# Croduino_Basic_v1_2.net
KiCad netlist of a schematic drawn in EAGLE
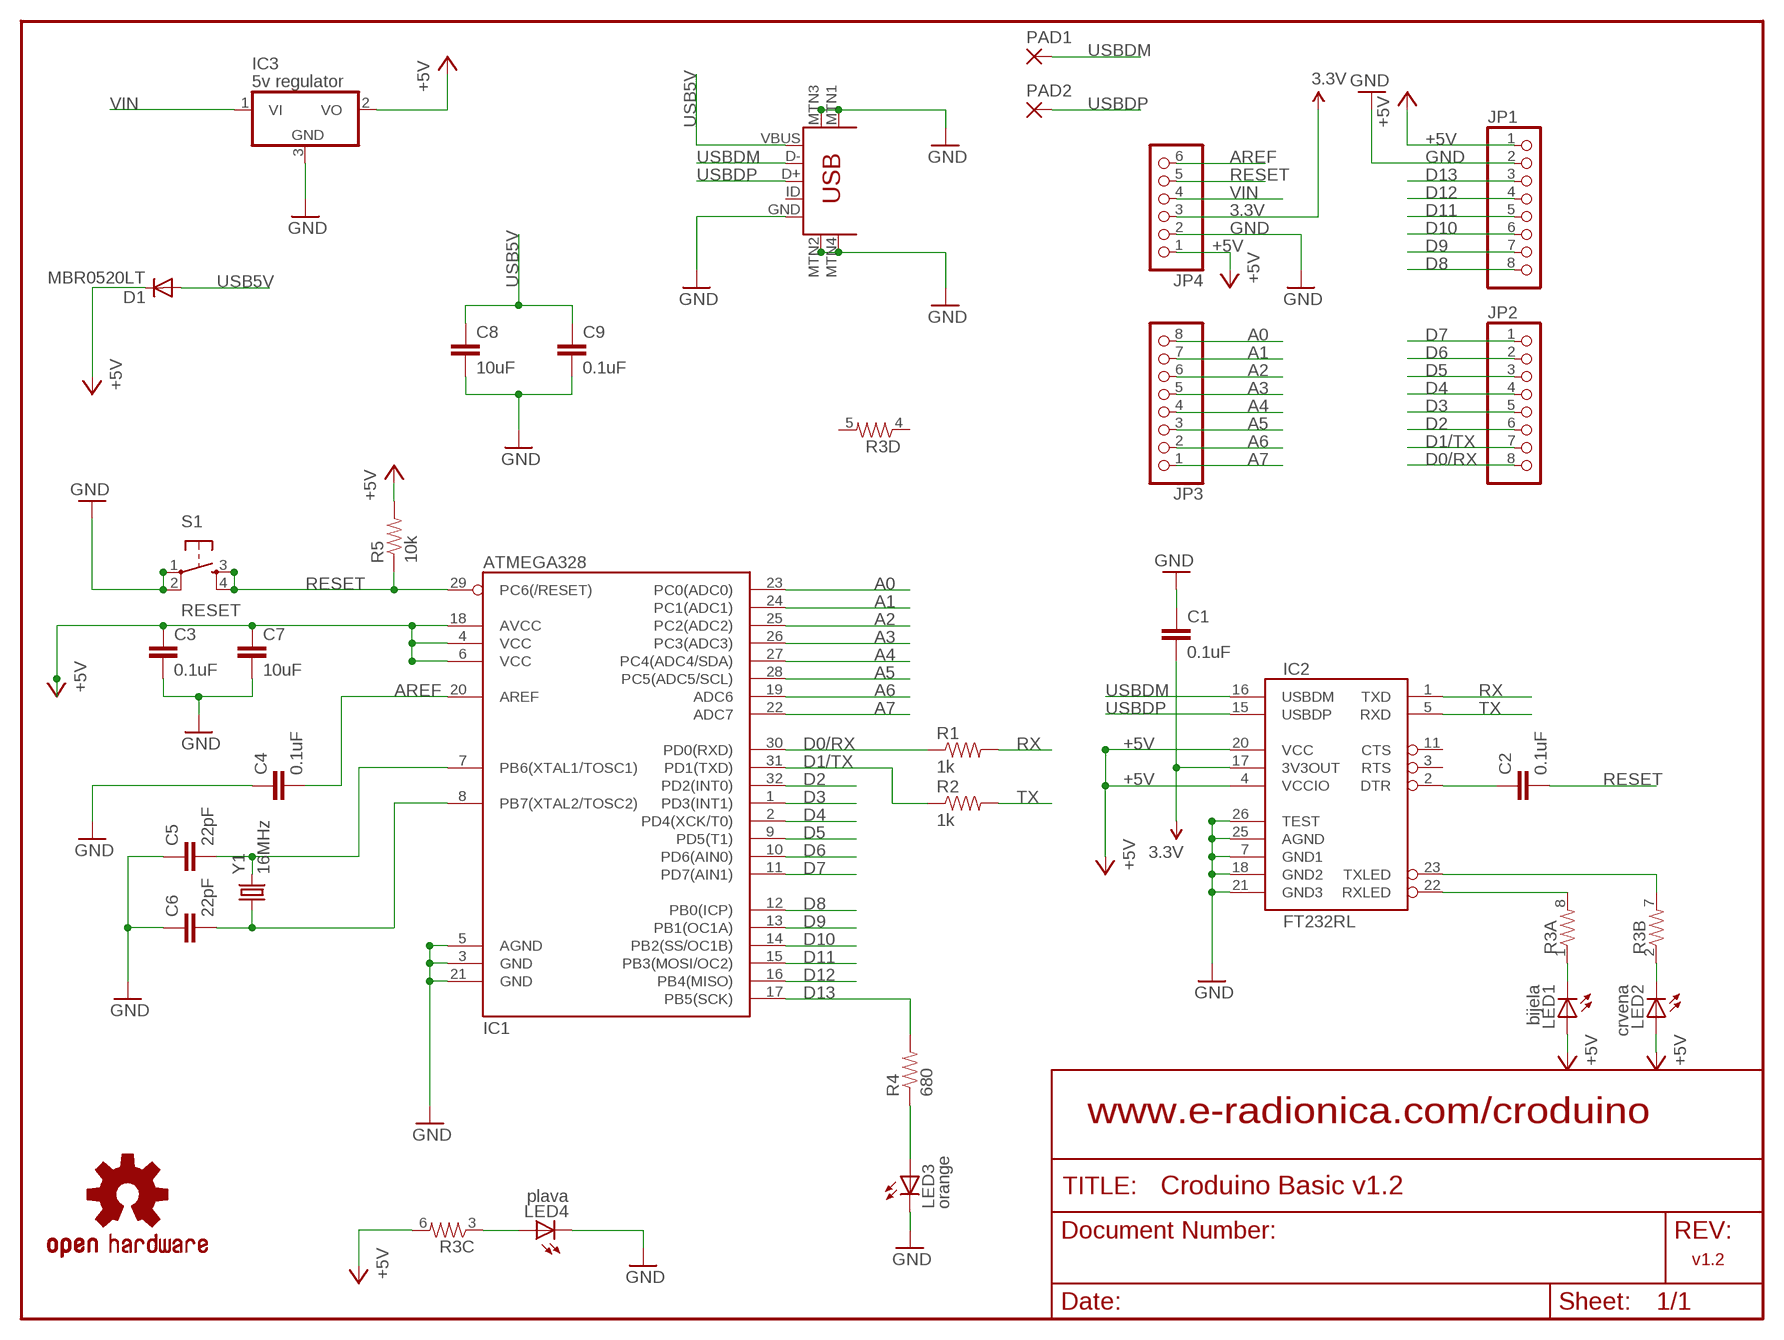
[diagram p0: schematic, sheet 1]

(export (version "E")
  (design (tool "Eeschema 10.0.6"))
  (components
    (comp (ref "C1")
      (value "0.1uF")
      (footprint "eagle-import:0603-CAP")
      (libsource (lib "eagle-import") (part "CAP0603-CAP"))
    )
    (comp (ref "C2")
      (value "0.1uF")
      (footprint "eagle-import:0603-CAP")
      (libsource (lib "eagle-import") (part "CAP0603-CAP"))
    )
    (comp (ref "C3")
      (value "0.1uF")
      (footprint "eagle-import:0603-CAP")
      (libsource (lib "eagle-import") (part "CAP0603-CAP"))
    )
    (comp (ref "C4")
      (value "0.1uF")
      (footprint "eagle-import:0603-CAP")
      (libsource (lib "eagle-import") (part "CAP0603-CAP"))
    )
    (comp (ref "C5")
      (value "22pF")
      (footprint "eagle-import:0603-CAP")
      (libsource (lib "eagle-import") (part "CAP0603-CAP"))
    )
    (comp (ref "C6")
      (value "22pF")
      (footprint "eagle-import:0603-CAP")
      (libsource (lib "eagle-import") (part "CAP0603-CAP"))
    )
    (comp (ref "C7")
      (value "10uF")
      (footprint "eagle-import:C3216")
      (libsource (lib "eagle-import") (part "C-EUC3216"))
    )
    (comp (ref "C8")
      (value "10uF")
      (footprint "eagle-import:C3216")
      (libsource (lib "eagle-import") (part "C-EUC3216"))
    )
    (comp (ref "C9")
      (value "0.1uF")
      (footprint "eagle-import:0603-CAP")
      (libsource (lib "eagle-import") (part "CAP0603-CAP"))
    )
    (comp (ref "D1")
      (value "MBR0520LT")
      (footprint "eagle-import:SOD123")
      (libsource (lib "eagle-import") (part "MBR0520LT"))
    )
    (comp (ref "IC1")
      (value "ATMEGA328")
      (footprint "eagle-import:TQFP32-08")
      (libsource (lib "eagle-import") (part "ATMEGA168"))
    )
    (comp (ref "IC2")
      (value "FT232RL")
      (footprint "eagle-import:SSOP28DB")
      (libsource (lib "eagle-import") (part "FT232RL-BASICSSOP"))
    )
    (comp (ref "IC3")
      (value "5v regulator")
      (footprint "eagle-import:TO252")
      (libsource (lib "eagle-import") (part "78DT05"))
    )
    (comp (ref "JP1")
      (value "PINHD-1X8BIG")
      (footprint "eagle-import:1X08-BIG")
      (libsource (lib "eagle-import") (part "PINHD-1X8BIG"))
    )
    (comp (ref "JP2")
      (value "PINHD-1X8BIG")
      (footprint "eagle-import:1X08-BIG")
      (libsource (lib "eagle-import") (part "PINHD-1X8BIG"))
    )
    (comp (ref "JP3")
      (value "PINHD-1X8BIG")
      (footprint "eagle-import:1X08-BIG")
      (libsource (lib "eagle-import") (part "PINHD-1X8BIG"))
    )
    (comp (ref "JP4")
      (value "PINHD-1X6B")
      (footprint "eagle-import:1X06-BIG")
      (libsource (lib "eagle-import") (part "PINHD-1X6B"))
    )
    (comp (ref "LED1")
      (value "bijela")
      (footprint "eagle-import:CHIP-LED0805")
      (libsource (lib "eagle-import") (part "LEDCHIP-LED0805"))
    )
    (comp (ref "LED2")
      (value "crvena")
      (footprint "eagle-import:CHIP-LED0805")
      (libsource (lib "eagle-import") (part "LEDCHIP-LED0805"))
    )
    (comp (ref "LED3")
      (value "orange")
      (footprint "eagle-import:CHIP-LED0805")
      (libsource (lib "eagle-import") (part "LEDCHIP-LED0805"))
    )
    (comp (ref "LED4")
      (value "plava")
      (footprint "eagle-import:CHIP-LED0805")
      (libsource (lib "eagle-import") (part "LEDCHIP-LED0805"))
    )
    (comp (ref "PAD1")
      (value "SMD2")
      (footprint "eagle-import:SMD1,27-2,54")
      (libsource (lib "eagle-import") (part "SMD2"))
    )
    (comp (ref "PAD2")
      (value "SMD2")
      (footprint "eagle-import:SMD1,27-2,54")
      (libsource (lib "eagle-import") (part "SMD2"))
    )
    (comp (ref "R1")
      (value "1k")
      (footprint "eagle-import:0603-RES")
      (libsource (lib "eagle-import") (part "RESISTOR0603-RES"))
    )
    (comp (ref "R2")
      (value "1k")
      (footprint "eagle-import:0603-RES")
      (libsource (lib "eagle-import") (part "RESISTOR0603-RES"))
    )
    (comp (ref "R3")
      (value "RESISTOR-ARRAY0603-ARV")
      (footprint "eagle-import:0603-ARV")
      (libsource (lib "eagle-import") (part "RESISTOR-ARRAY0603-ARV"))
    )
    (comp (ref "R4")
      (value "680")
      (footprint "eagle-import:0603-RES")
      (libsource (lib "eagle-import") (part "RESISTOR0603-RES"))
    )
    (comp (ref "R5")
      (value "10k")
      (footprint "eagle-import:0603-RES")
      (libsource (lib "eagle-import") (part "RESISTOR0603-RES"))
    )
    (comp (ref "S1")
      (value "RESET")
      (footprint "eagle-import:TACTILE_SWITCH_SMD")
      (libsource (lib "eagle-import") (part "TAC_SWITCHSMD"))
    )
    (comp (ref "U$5")
      (value "OSHW-LOGOS")
      (footprint "eagle-import:OSHW-LOGO-S")
      (libsource (lib "eagle-import") (part "OSHW-LOGOS"))
    )
    (comp (ref "U1")
      (value "USB-MINIB")
      (footprint "eagle-import:USB-MINIB")
      (libsource (lib "eagle-import") (part "USB-MINIB-5PIN"))
    )
    (comp (ref "Y1")
      (value "16MHz")
      (footprint "eagle-import:CRYSTAL-SMD-5X3")
      (libsource (lib "eagle-import") (part "CRYSTAL5X3"))
    )
  )
  (nets
    (net (code "1") (name "+5V") (class "Default")
      (node (ref "C3") (pin "1") (pinfunction "1_1") (pintype "passive"))
      (node (ref "C7") (pin "1") (pinfunction "1_1") (pintype "passive"))
      (node (ref "D1") (pin "C") (pinfunction "C_C") (pintype "passive"))
      (node (ref "IC1") (pin "18") (pinfunction "AVCC_18") (pintype "bidirectional"))
      (node (ref "IC1") (pin "4") (pinfunction "VCC_4") (pintype "bidirectional"))
      (node (ref "IC1") (pin "6") (pinfunction "VCC_6") (pintype "bidirectional"))
      (node (ref "IC2") (pin "20") (pinfunction "VCC_20") (pintype "power_in"))
      (node (ref "IC2") (pin "4") (pinfunction "VCCIO_4") (pintype "power_in"))
      (node (ref "IC3") (pin "2") (pinfunction "VO_2") (pintype "passive"))
      (node (ref "JP1") (pin "1") (pinfunction "1_1") (pintype "passive"))
      (node (ref "JP4") (pin "1") (pinfunction "1_1") (pintype "passive"))
      (node (ref "LED1") (pin "A") (pinfunction "A_A") (pintype "passive"))
      (node (ref "LED2") (pin "A") (pinfunction "A_A") (pintype "passive"))
      (node (ref "R3") (pin "6") (pinfunction "2_6") (pintype "passive"))
      (node (ref "R5") (pin "2") (pinfunction "2_2") (pintype "passive"))
    )
    (net (code "2") (name "/A0") (class "Default")
      (node (ref "IC1") (pin "23") (pinfunction "PC0(ADC0)_23") (pintype "bidirectional"))
      (node (ref "JP3") (pin "8") (pinfunction "8_8") (pintype "passive"))
    )
    (net (code "3") (name "/A1") (class "Default")
      (node (ref "IC1") (pin "24") (pinfunction "PC1(ADC1)_24") (pintype "bidirectional"))
      (node (ref "JP3") (pin "7") (pinfunction "7_7") (pintype "passive"))
    )
    (net (code "4") (name "/A2") (class "Default")
      (node (ref "IC1") (pin "25") (pinfunction "PC2(ADC2)_25") (pintype "bidirectional"))
      (node (ref "JP3") (pin "6") (pinfunction "6_6") (pintype "passive"))
    )
    (net (code "5") (name "/A3") (class "Default")
      (node (ref "IC1") (pin "26") (pinfunction "PC3(ADC3)_26") (pintype "bidirectional"))
      (node (ref "JP3") (pin "5") (pinfunction "5_5") (pintype "passive"))
    )
    (net (code "6") (name "/A4") (class "Default")
      (node (ref "IC1") (pin "27") (pinfunction "PC4(ADC4/SDA)_27") (pintype "bidirectional"))
      (node (ref "JP3") (pin "4") (pinfunction "4_4") (pintype "passive"))
    )
    (net (code "7") (name "/A5") (class "Default")
      (node (ref "IC1") (pin "28") (pinfunction "PC5(ADC5/SCL)_28") (pintype "bidirectional"))
      (node (ref "JP3") (pin "3") (pinfunction "3_3") (pintype "passive"))
    )
    (net (code "8") (name "/A6") (class "Default")
      (node (ref "IC1") (pin "19") (pinfunction "ADC6_19") (pintype "bidirectional"))
      (node (ref "JP3") (pin "2") (pinfunction "2_2") (pintype "passive"))
    )
    (net (code "9") (name "/A7") (class "Default")
      (node (ref "IC1") (pin "22") (pinfunction "ADC7_22") (pintype "bidirectional"))
      (node (ref "JP3") (pin "1") (pinfunction "1_1") (pintype "passive"))
    )
    (net (code "10") (name "/AREF") (class "Default")
      (node (ref "C4") (pin "2") (pinfunction "2_2") (pintype "passive"))
      (node (ref "IC1") (pin "20") (pinfunction "AREF_20") (pintype "bidirectional"))
      (node (ref "JP4") (pin "6") (pinfunction "6_6") (pintype "passive"))
    )
    (net (code "11") (name "/D0{slash}RX") (class "Default")
      (node (ref "IC1") (pin "30") (pinfunction "PD0(RXD)_30") (pintype "bidirectional"))
      (node (ref "JP2") (pin "8") (pinfunction "8_8") (pintype "passive"))
      (node (ref "R1") (pin "1") (pinfunction "1_1") (pintype "passive"))
    )
    (net (code "12") (name "/D1{slash}TX") (class "Default")
      (node (ref "IC1") (pin "31") (pinfunction "PD1(TXD)_31") (pintype "bidirectional"))
      (node (ref "JP2") (pin "7") (pinfunction "7_7") (pintype "passive"))
      (node (ref "R2") (pin "1") (pinfunction "1_1") (pintype "passive"))
    )
    (net (code "13") (name "/D2") (class "Default")
      (node (ref "IC1") (pin "32") (pinfunction "PD2(INT0)_32") (pintype "bidirectional"))
      (node (ref "JP2") (pin "6") (pinfunction "6_6") (pintype "passive"))
    )
    (net (code "14") (name "/D3") (class "Default")
      (node (ref "IC1") (pin "1") (pinfunction "PD3(INT1)_1") (pintype "bidirectional"))
      (node (ref "JP2") (pin "5") (pinfunction "5_5") (pintype "passive"))
    )
    (net (code "15") (name "/D4") (class "Default")
      (node (ref "IC1") (pin "2") (pinfunction "PD4(XCK/T0)_2") (pintype "bidirectional"))
      (node (ref "JP2") (pin "4") (pinfunction "4_4") (pintype "passive"))
    )
    (net (code "16") (name "/D5") (class "Default")
      (node (ref "IC1") (pin "9") (pinfunction "PD5(T1)_9") (pintype "bidirectional"))
      (node (ref "JP2") (pin "3") (pinfunction "3_3") (pintype "passive"))
    )
    (net (code "17") (name "/D6") (class "Default")
      (node (ref "IC1") (pin "10") (pinfunction "PD6(AIN0)_10") (pintype "bidirectional"))
      (node (ref "JP2") (pin "2") (pinfunction "2_2") (pintype "passive"))
    )
    (net (code "18") (name "/D7") (class "Default")
      (node (ref "IC1") (pin "11") (pinfunction "PD7(AIN1)_11") (pintype "bidirectional"))
      (node (ref "JP2") (pin "1") (pinfunction "1_1") (pintype "passive"))
    )
    (net (code "19") (name "/D8") (class "Default")
      (node (ref "IC1") (pin "12") (pinfunction "PB0(ICP)_12") (pintype "bidirectional"))
      (node (ref "JP1") (pin "8") (pinfunction "8_8") (pintype "passive"))
    )
    (net (code "20") (name "/D9") (class "Default")
      (node (ref "IC1") (pin "13") (pinfunction "PB1(OC1A)_13") (pintype "bidirectional"))
      (node (ref "JP1") (pin "7") (pinfunction "7_7") (pintype "passive"))
    )
    (net (code "21") (name "/D10") (class "Default")
      (node (ref "IC1") (pin "14") (pinfunction "PB2(SS/OC1B)_14") (pintype "bidirectional"))
      (node (ref "JP1") (pin "6") (pinfunction "6_6") (pintype "passive"))
    )
    (net (code "22") (name "/D11") (class "Default")
      (node (ref "IC1") (pin "15") (pinfunction "PB3(MOSI/OC2)_15") (pintype "bidirectional"))
      (node (ref "JP1") (pin "5") (pinfunction "5_5") (pintype "passive"))
    )
    (net (code "23") (name "/D12") (class "Default")
      (node (ref "IC1") (pin "16") (pinfunction "PB4(MISO)_16") (pintype "bidirectional"))
      (node (ref "JP1") (pin "4") (pinfunction "4_4") (pintype "passive"))
    )
    (net (code "24") (name "/D13") (class "Default")
      (node (ref "IC1") (pin "17") (pinfunction "PB5(SCK)_17") (pintype "bidirectional"))
      (node (ref "JP1") (pin "3") (pinfunction "3_3") (pintype "passive"))
      (node (ref "R4") (pin "2") (pinfunction "2_2") (pintype "passive"))
    )
    (net (code "25") (name "/RESET") (class "Default")
      (node (ref "C2") (pin "2") (pinfunction "2_2") (pintype "passive"))
      (node (ref "IC1") (pin "29") (pinfunction "PC6(/RESET)_29") (pintype "bidirectional"))
      (node (ref "JP4") (pin "5") (pinfunction "5_5") (pintype "passive"))
      (node (ref "R5") (pin "1") (pinfunction "1_1") (pintype "passive"))
      (node (ref "S1") (pin "3") (pinfunction "3_3") (pintype "passive"))
      (node (ref "S1") (pin "4") (pinfunction "4_4") (pintype "passive"))
    )
    (net (code "26") (name "/RX") (class "Default")
      (node (ref "IC2") (pin "1") (pinfunction "TXD_1") (pintype "output"))
      (node (ref "R1") (pin "2") (pinfunction "2_2") (pintype "passive"))
    )
    (net (code "27") (name "/TX") (class "Default")
      (node (ref "IC2") (pin "5") (pinfunction "RXD_5") (pintype "input"))
      (node (ref "R2") (pin "2") (pinfunction "2_2") (pintype "passive"))
    )
    (net (code "28") (name "/USB5V") (class "Default")
      (node (ref "C8") (pin "1") (pinfunction "1_1") (pintype "passive"))
      (node (ref "C9") (pin "1") (pinfunction "1_1") (pintype "passive"))
      (node (ref "D1") (pin "A") (pinfunction "A_A") (pintype "passive"))
      (node (ref "U1") (pin "VBUS") (pinfunction "VBUS_VBUS") (pintype "bidirectional"))
    )
    (net (code "29") (name "/USBDM") (class "Default")
      (node (ref "IC2") (pin "16") (pinfunction "USBDM_16") (pintype "bidirectional"))
      (node (ref "PAD1") (pin "1") (pinfunction "P_1") (pintype "passive"))
      (node (ref "U1") (pin "D-") (pinfunction "D-_D-") (pintype "bidirectional"))
    )
    (net (code "30") (name "/USBDP") (class "Default")
      (node (ref "IC2") (pin "15") (pinfunction "USBDP_15") (pintype "bidirectional"))
      (node (ref "PAD2") (pin "1") (pinfunction "P_1") (pintype "passive"))
      (node (ref "U1") (pin "D+") (pinfunction "D+_D+") (pintype "bidirectional"))
    )
    (net (code "31") (name "/VIN") (class "Default")
      (node (ref "IC3") (pin "1") (pinfunction "VI_1") (pintype "input"))
      (node (ref "JP4") (pin "4") (pinfunction "4_4") (pintype "passive"))
    )
    (net (code "32") (name "3.3V") (class "Default")
      (node (ref "C1") (pin "2") (pinfunction "2_2") (pintype "passive"))
      (node (ref "IC2") (pin "17") (pinfunction "3V3OUT_17") (pintype "output"))
      (node (ref "JP4") (pin "3") (pinfunction "3_3") (pintype "passive"))
    )
    (net (code "33") (name "GND") (class "Default")
      (node (ref "C1") (pin "1") (pinfunction "1_1") (pintype "passive"))
      (node (ref "C3") (pin "2") (pinfunction "2_2") (pintype "passive"))
      (node (ref "C4") (pin "1") (pinfunction "1_1") (pintype "passive"))
      (node (ref "C5") (pin "1") (pinfunction "1_1") (pintype "passive"))
      (node (ref "C6") (pin "1") (pinfunction "1_1") (pintype "passive"))
      (node (ref "C7") (pin "2") (pinfunction "2_2") (pintype "passive"))
      (node (ref "C8") (pin "2") (pinfunction "2_2") (pintype "passive"))
      (node (ref "C9") (pin "2") (pinfunction "2_2") (pintype "passive"))
      (node (ref "IC1") (pin "21") (pinfunction "GND_21") (pintype "bidirectional"))
      (node (ref "IC1") (pin "3") (pinfunction "GND_3") (pintype "bidirectional"))
      (node (ref "IC1") (pin "5") (pinfunction "AGND_5") (pintype "bidirectional"))
      (node (ref "IC2") (pin "18") (pinfunction "GND2_18") (pintype "power_in"))
      (node (ref "IC2") (pin "21") (pinfunction "GND3_21") (pintype "power_in"))
      (node (ref "IC2") (pin "25") (pinfunction "AGND_25") (pintype "power_in"))
      (node (ref "IC2") (pin "26") (pinfunction "TEST_26") (pintype "input"))
      (node (ref "IC2") (pin "7") (pinfunction "GND1_7") (pintype "power_in"))
      (node (ref "IC3") (pin "3") (pinfunction "GND_3") (pintype "passive"))
      (node (ref "JP1") (pin "2") (pinfunction "2_2") (pintype "passive"))
      (node (ref "JP4") (pin "2") (pinfunction "2_2") (pintype "passive"))
      (node (ref "LED3") (pin "C") (pinfunction "C_C") (pintype "passive"))
      (node (ref "LED4") (pin "C") (pinfunction "C_C") (pintype "passive"))
      (node (ref "S1") (pin "1") (pinfunction "1_1") (pintype "passive"))
      (node (ref "S1") (pin "2") (pinfunction "2_2") (pintype "passive"))
      (node (ref "U1") (pin "GND") (pinfunction "GND_GND") (pintype "bidirectional"))
      (node (ref "U1") (pin "MTN1") (pinfunction "MTN2_MTN1") (pintype "bidirectional"))
      (node (ref "U1") (pin "MTN2") (pinfunction "MTN3_MTN2") (pintype "bidirectional"))
      (node (ref "U1") (pin "MTN3") (pinfunction "MTN1_MTN3") (pintype "bidirectional"))
      (node (ref "U1") (pin "MTN4") (pinfunction "MTN4_MTN4") (pintype "bidirectional"))
    )
    (net (code "34") (name "Net-(IC1-PB6(XTAL1{slash}TOSC1))") (class "Default")
      (node (ref "C5") (pin "2") (pinfunction "2_2") (pintype "passive"))
      (node (ref "IC1") (pin "7") (pinfunction "PB6(XTAL1/TOSC1)_7") (pintype "bidirectional"))
      (node (ref "Y1") (pin "3") (pinfunction "2_3") (pintype "passive"))
    )
    (net (code "35") (name "Net-(IC1-PB7(XTAL2{slash}TOSC2))") (class "Default")
      (node (ref "C6") (pin "2") (pinfunction "2_2") (pintype "passive"))
      (node (ref "IC1") (pin "8") (pinfunction "PB7(XTAL2/TOSC2)_8") (pintype "bidirectional"))
      (node (ref "Y1") (pin "1") (pinfunction "1_1") (pintype "passive"))
    )
    (net (code "36") (name "Net-(IC2-DTR)") (class "Default")
      (node (ref "C2") (pin "1") (pinfunction "1_1") (pintype "passive"))
      (node (ref "IC2") (pin "2") (pinfunction "DTR_2") (pintype "bidirectional"))
    )
    (net (code "37") (name "Net-(IC2-RXLED)") (class "Default")
      (node (ref "IC2") (pin "22") (pinfunction "RXLED_22") (pintype "bidirectional"))
      (node (ref "R3") (pin "8") (pinfunction "2_8") (pintype "passive"))
    )
    (net (code "38") (name "Net-(IC2-TXLED)") (class "Default")
      (node (ref "IC2") (pin "23") (pinfunction "TXLED_23") (pintype "bidirectional"))
      (node (ref "R3") (pin "7") (pinfunction "2_7") (pintype "passive"))
    )
    (net (code "39") (name "Net-(LED1-PadC)") (class "Default")
      (node (ref "LED1") (pin "C") (pinfunction "C_C") (pintype "passive"))
      (node (ref "R3") (pin "1") (pinfunction "1_1") (pintype "passive"))
    )
    (net (code "40") (name "Net-(LED3-PadA)") (class "Default")
      (node (ref "LED3") (pin "A") (pinfunction "A_A") (pintype "passive"))
      (node (ref "R4") (pin "1") (pinfunction "1_1") (pintype "passive"))
    )
    (net (code "41") (name "Net-(R3B-1)") (class "Default")
      (node (ref "LED2") (pin "C") (pinfunction "C_C") (pintype "passive"))
      (node (ref "R3") (pin "2") (pinfunction "1_2") (pintype "passive"))
    )
    (net (code "42") (name "Net-(R3C-1)") (class "Default")
      (node (ref "LED4") (pin "A") (pinfunction "A_A") (pintype "passive"))
      (node (ref "R3") (pin "3") (pinfunction "1_3") (pintype "passive"))
    )
    (net (code "43") (name "unconnected-(IC2-CTS-Pad11)") (class "Default")
      (node (ref "IC2") (pin "11") (pinfunction "CTS_11") (pintype "bidirectional"))
    )
    (net (code "44") (name "unconnected-(IC2-RTS-Pad3)") (class "Default")
      (node (ref "IC2") (pin "3") (pinfunction "RTS_3") (pintype "bidirectional"))
    )
    (net (code "45") (name "unconnected-(R3D-1-Pad4)") (class "Default")
      (node (ref "R3") (pin "4") (pinfunction "1_4") (pintype "passive"))
    )
    (net (code "46") (name "unconnected-(R3D-2-Pad5)") (class "Default")
      (node (ref "R3") (pin "5") (pinfunction "2_5") (pintype "passive"))
    )
    (net (code "47") (name "unconnected-(U1-PadID)") (class "Default")
      (node (ref "U1") (pin "ID") (pinfunction "ID_ID") (pintype "bidirectional"))
    )
  )
)
